# breakout.net
KiCad netlist of a schematic drawn in EAGLE
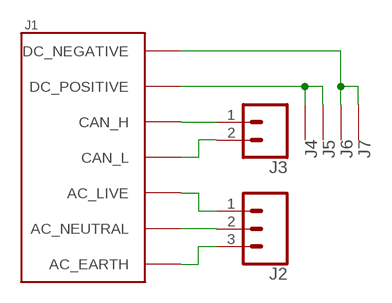
[diagram p0: schematic, sheet 1]

(export (version "E")
  (design (tool "Eeschema 10.0.6"))
  (components
    (comp (ref "J1")
      (value "FLATPACK2_CON")
      (footprint "eagle-import:FLATPACK2_CON")
      (libsource (lib "eagle-import") (part "FLATPACK2_CON"))
    )
    (comp (ref "J2")
      (value "WEIDMULLER_PM_508")
      (footprint "eagle-import:WEIDMULLER_PM_508")
      (libsource (lib "eagle-import") (part "WEIDMULLER_PM_508"))
    )
    (comp (ref "J3")
      (value "CONN_021X02_NO_SILK")
      (footprint "eagle-import:1X02_NO_SILK")
      (libsource (lib "eagle-import") (part "CONN_021X02_NO_SILK"))
    )
    (comp (ref "J4")
      (value "FLATPACK2_DC_LUG")
      (footprint "eagle-import:FLATPACK2_DC_LUG")
      (libsource (lib "eagle-import") (part "FLATPACK2_DC_LUG"))
    )
    (comp (ref "J5")
      (value "FLATPACK2_DC_LUG")
      (footprint "eagle-import:FLATPACK2_DC_LUG")
      (libsource (lib "eagle-import") (part "FLATPACK2_DC_LUG"))
    )
    (comp (ref "J6")
      (value "FLATPACK2_DC_LUG")
      (footprint "eagle-import:FLATPACK2_DC_LUG")
      (libsource (lib "eagle-import") (part "FLATPACK2_DC_LUG"))
    )
    (comp (ref "J7")
      (value "FLATPACK2_DC_LUG")
      (footprint "eagle-import:FLATPACK2_DC_LUG")
      (libsource (lib "eagle-import") (part "FLATPACK2_DC_LUG"))
    )
  )
  (nets
    (net (code "1") (name "Net-(J1-AC_LIVE-PadAC_LIVE_BOTTOM)") (class "Default")
      (node (ref "J1") (pin "AC_LIVE_BOTTOM") (pinfunction "AC_LIVE_AC_LIVE_BOTTOM") (pintype "input"))
      (node (ref "J1") (pin "AC_LIVE_TOP") (pinfunction "AC_LIVE_AC_LIVE_TOP") (pintype "input"))
      (node (ref "J2") (pin "1") (pinfunction "1_1") (pintype "passive"))
    )
    (net (code "2") (name "Net-(J1-AC_NEUTRAL-PadAC_NEUTRAL_BOTTOM)") (class "Default")
      (node (ref "J1") (pin "AC_NEUTRAL_BOTTOM") (pinfunction "AC_NEUTRAL_AC_NEUTRAL_BOTTOM") (pintype "input"))
      (node (ref "J1") (pin "AC_NEUTRAL_TOP") (pinfunction "AC_NEUTRAL_AC_NEUTRAL_TOP") (pintype "input"))
      (node (ref "J2") (pin "2") (pinfunction "2_2") (pintype "passive"))
    )
    (net (code "3") (name "Net-(J1-CAN_H)") (class "Default")
      (node (ref "J1") (pin "CAN_H_TOP") (pinfunction "CAN_H_CAN_H_TOP") (pintype "bidirectional"))
      (node (ref "J3") (pin "1") (pinfunction "1_1") (pintype "passive"))
    )
    (net (code "4") (name "Net-(J1-CAN_L)") (class "Default")
      (node (ref "J1") (pin "CAN_L_TOP") (pinfunction "CAN_L_CAN_L_TOP") (pintype "bidirectional"))
      (node (ref "J3") (pin "2") (pinfunction "2_2") (pintype "passive"))
    )
    (net (code "5") (name "Net-(J1-PadAC_EARTH)") (class "Default")
      (node (ref "J1") (pin "AC_EARTH") (pinfunction "AC_EARTH_AC_EARTH") (pintype "input"))
      (node (ref "J2") (pin "3") (pinfunction "3_3") (pintype "passive"))
    )
    (net (code "6") (name "Net-(J4-PIN)") (class "Default")
      (node (ref "J1") (pin "DC_POSITIVE_BOTTOM") (pinfunction "DC_POSITIVE_DC_POSITIVE_BOTTOM") (pintype "output"))
      (node (ref "J1") (pin "DC_POSITIVE_TOP") (pinfunction "DC_POSITIVE_DC_POSITIVE_TOP") (pintype "output"))
      (node (ref "J4") (pin "P$1") (pinfunction "PIN_P$1") (pintype "passive"))
      (node (ref "J5") (pin "P$1") (pinfunction "PIN_P$1") (pintype "passive"))
    )
    (net (code "7") (name "Net-(J6-PIN)") (class "Default")
      (node (ref "J1") (pin "DC_NEGATIVE_BOTTOM") (pinfunction "DC_NEGATIVE_DC_NEGATIVE_BOTTOM") (pintype "output"))
      (node (ref "J1") (pin "DC_NEGATIVE_TOP") (pinfunction "DC_NEGATIVE_DC_NEGATIVE_TOP") (pintype "output"))
      (node (ref "J6") (pin "P$1") (pinfunction "PIN_P$1") (pintype "passive"))
      (node (ref "J7") (pin "P$1") (pinfunction "PIN_P$1") (pintype "passive"))
    )
  )
)
